# PCB_Fungnator.net
KiCad netlist of a schematic drawn in Altium Designer
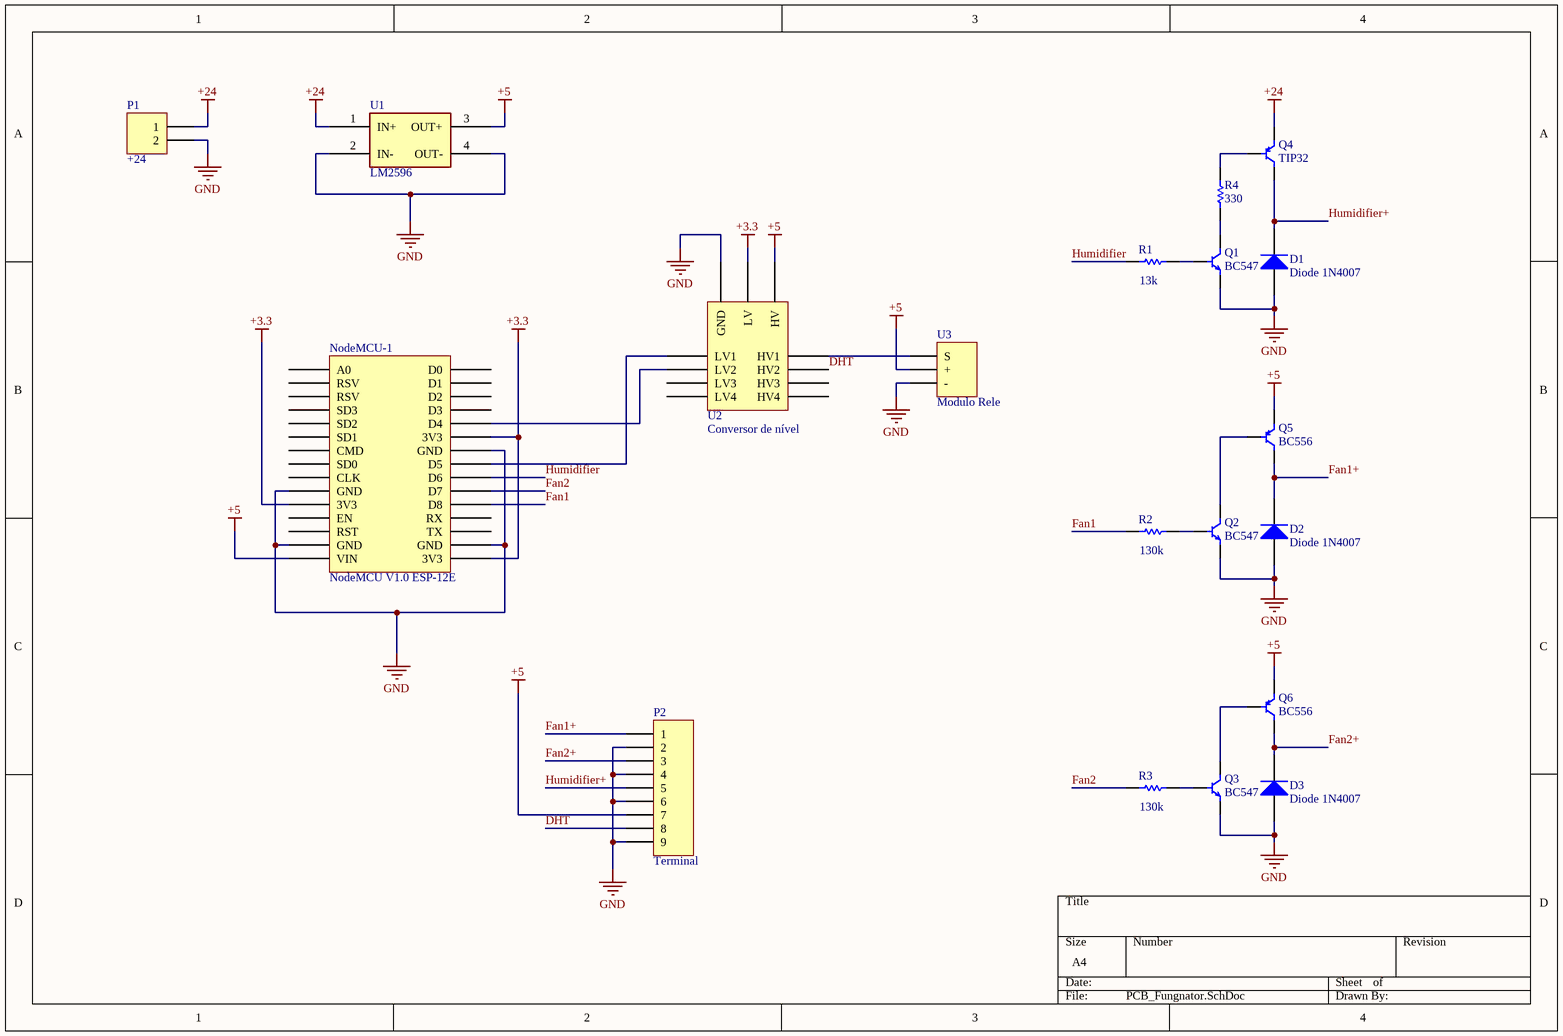
[diagram p0: PCB_Fungnator.SchDoc]

(export (version "E")
  (design (tool "Eeschema 10.0.6"))
  (components
    (comp (ref "D1")
      (value "Diode 1N4007")
      (footprint "DO-41")
      (description "1 Amp General Purpose Rectifier")
      (fields (field (name "PUBLISHER") "Altium Limited"))
      (libsource (lib "Miscellaneous Devices") (part "Diode 1N4007"))
    )
    (comp (ref "D2")
      (value "Diode 1N4007")
      (footprint "DO-41")
      (description "1 Amp General Purpose Rectifier")
      (fields (field (name "PUBLISHER") "Altium Limited"))
      (libsource (lib "Miscellaneous Devices") (part "Diode 1N4007"))
    )
    (comp (ref "D3")
      (value "Diode 1N4007")
      (footprint "DO-41")
      (description "1 Amp General Purpose Rectifier")
      (fields (field (name "PUBLISHER") "Altium Limited"))
      (libsource (lib "Miscellaneous Devices") (part "Diode 1N4007"))
    )
    (comp (ref "NodeMCU-1")
      (value "NodeMCU V1.0 ESP-12E")
      (footprint "NodeMCU V1.0 ESP-12E")
      (description "NodeMCU V1.0 ESP8266 (ESP-12E)")
      (libsource (lib "nodemcu") (part "NodeMCU V1.0 ESP-12E"))
    )
    (comp (ref "P1")
      (value "+24")
      (footprint "KRE_2")
      (description "Terminal Block 1x2")
      (libsource (lib "GPDSE") (part "KRE_2"))
    )
    (comp (ref "P2")
      (value "Terminal")
      (footprint "KRE_9")
      (description "Terminal Block 1x9")
      (libsource (lib "GPDSE") (part "KRE_9"))
    )
    (comp (ref "Q1")
      (value "BC547")
      (footprint "TO-92/CBE")
      (description "NPN Epitaxial Silicon Transistor")
      (fields (field (name "COMPLEMENTARY PART") "BC557"))
      (libsource (lib "GPDSE") (part "BC547"))
    )
    (comp (ref "Q2")
      (value "BC547")
      (footprint "TO-92/CBE")
      (description "NPN Epitaxial Silicon Transistor")
      (fields (field (name "COMPLEMENTARY PART") "BC557"))
      (libsource (lib "GPDSE") (part "BC547"))
    )
    (comp (ref "Q3")
      (value "BC547")
      (footprint "TO-92/CBE")
      (description "NPN Epitaxial Silicon Transistor")
      (fields (field (name "COMPLEMENTARY PART") "BC557"))
      (libsource (lib "GPDSE") (part "BC547"))
    )
    (comp (ref "Q4")
      (value "TIP32")
      (footprint "TO-220/BCE")
      (description "PNP Epitaxial Silicon Transistor")
      (fields (field (name "COMPLEMENTARY PART") "TIP31"))
      (libsource (lib "GPDSE") (part "TIP32"))
    )
    (comp (ref "Q5")
      (value "BC556")
      (footprint "TO-92/CBE")
      (description "PNP Epitaxial Silicon Transistor")
      (fields (field (name "COMPLEMENTARY PART") "BC546"))
      (libsource (lib "GPDSE") (part "BC556"))
    )
    (comp (ref "Q6")
      (value "BC556")
      (footprint "TO-92/CBE")
      (description "PNP Epitaxial Silicon Transistor")
      (fields (field (name "COMPLEMENTARY PART") "BC546"))
      (libsource (lib "GPDSE") (part "BC556"))
    )
    (comp (ref "R1")
      (value "13k")
      (footprint "AXIAL-0.3")
      (description "Resistor")
      (fields (field (name "Comment") "Res1") (field (name "PUBLISHER") "Altium Limited"))
      (libsource (lib "Miscellaneous Devices") (part "Res1"))
    )
    (comp (ref "R2")
      (value "130k")
      (footprint "AXIAL-0.3")
      (description "Resistor")
      (fields (field (name "Comment") "Res1") (field (name "PUBLISHER") "Altium Limited"))
      (libsource (lib "Miscellaneous Devices") (part "Res1"))
    )
    (comp (ref "R3")
      (value "130k")
      (footprint "AXIAL-0.3")
      (description "Resistor")
      (fields (field (name "Comment") "Res1") (field (name "PUBLISHER") "Altium Limited"))
      (libsource (lib "Miscellaneous Devices") (part "Res1"))
    )
    (comp (ref "R4")
      (value "330")
      (footprint "AXIAL-0.3")
      (description "Resistor")
      (fields (field (name "Comment") "Res1") (field (name "PUBLISHER") "Altium Limited"))
      (libsource (lib "Miscellaneous Devices") (part "Res1"))
    )
    (comp (ref "U1") (value "LM2596") (footprint "LM2596") (libsource (lib "Schlib1") (part "LM2596")))
    (comp (ref "U2")
      (value "Conversor de nível")
      (footprint "Conversor_Nivel")
      (libsource (lib "Schlib1") (part "Conversor de nível"))
    )
    (comp (ref "U3")
      (value "Modulo Rele")
      (footprint "MODULO_RELE")
      (libsource (lib "Schlib1") (part "Modulo Rele"))
    )
  )
  (nets
    (net (code "1") (name "+3.3") (class "Default")
      (node (ref "NodeMCU-1") (pin "3V3") (pinfunction "3V3_3V3") (pintype "passive"))
      (node (ref "U2") (pin "3") (pinfunction "LV_3") (pintype "passive"))
    )
    (net (code "2") (name "+5") (class "Default")
      (node (ref "NodeMCU-1") (pin "VIN") (pinfunction "VIN_VIN") (pintype "passive"))
      (node (ref "P2") (pin "7") (pinfunction "7_7") (pintype "passive"))
      (node (ref "Q5") (pin "E") (pinfunction "E_E") (pintype "passive"))
      (node (ref "Q6") (pin "E") (pinfunction "E_E") (pintype "passive"))
      (node (ref "U1") (pin "3") (pinfunction "OUT+_3") (pintype "passive"))
      (node (ref "U2") (pin "9") (pinfunction "HV_9") (pintype "passive"))
      (node (ref "U3") (pin "2") (pinfunction "+_2") (pintype "passive"))
    )
    (net (code "3") (name "+24") (class "Default")
      (node (ref "P1") (pin "1") (pinfunction "1_1") (pintype "passive"))
      (node (ref "Q4") (pin "E") (pinfunction "E_E") (pintype "passive"))
      (node (ref "U1") (pin "1") (pinfunction "IN+_1") (pintype "passive"))
    )
    (net (code "4") (name "/DHT") (class "Default")
      (node (ref "P2") (pin "8") (pinfunction "8_8") (pintype "passive"))
      (node (ref "U2") (pin "8") (pinfunction "HV2_8") (pintype "passive"))
    )
    (net (code "5") (name "/Fan1") (class "Default")
      (node (ref "NodeMCU-1") (pin "D8") (pinfunction "D8_D8") (pintype "passive"))
      (node (ref "R2") (pin "1") (pinfunction "1_1") (pintype "passive"))
    )
    (net (code "6") (name "/Fan1+") (class "Default")
      (node (ref "D2") (pin "2") (pinfunction "K_2") (pintype "passive"))
      (node (ref "P2") (pin "1") (pinfunction "1_1") (pintype "passive"))
      (node (ref "Q5") (pin "C") (pinfunction "C_C") (pintype "passive"))
    )
    (net (code "7") (name "/Fan2") (class "Default")
      (node (ref "NodeMCU-1") (pin "D7") (pinfunction "D7_D7") (pintype "passive"))
      (node (ref "R3") (pin "1") (pinfunction "1_1") (pintype "passive"))
    )
    (net (code "8") (name "/Fan2+") (class "Default")
      (node (ref "D3") (pin "2") (pinfunction "K_2") (pintype "passive"))
      (node (ref "P2") (pin "3") (pinfunction "3_3") (pintype "passive"))
      (node (ref "Q6") (pin "C") (pinfunction "C_C") (pintype "passive"))
    )
    (net (code "9") (name "/Humidifier") (class "Default")
      (node (ref "NodeMCU-1") (pin "D6") (pinfunction "D6_D6") (pintype "passive"))
      (node (ref "R1") (pin "1") (pinfunction "1_1") (pintype "passive"))
    )
    (net (code "10") (name "/Humidifier+") (class "Default")
      (node (ref "D1") (pin "2") (pinfunction "K_2") (pintype "passive"))
      (node (ref "P2") (pin "5") (pinfunction "5_5") (pintype "passive"))
      (node (ref "Q4") (pin "C") (pinfunction "C_C") (pintype "passive"))
    )
    (net (code "11") (name "GND") (class "Default")
      (node (ref "D1") (pin "1") (pinfunction "A_1") (pintype "passive"))
      (node (ref "D2") (pin "1") (pinfunction "A_1") (pintype "passive"))
      (node (ref "D3") (pin "1") (pinfunction "A_1") (pintype "passive"))
      (node (ref "NodeMCU-1") (pin "GND") (pinfunction "GND_GND") (pintype "passive"))
      (node (ref "P1") (pin "2") (pinfunction "2_2") (pintype "passive"))
      (node (ref "P2") (pin "2") (pinfunction "2_2") (pintype "passive"))
      (node (ref "P2") (pin "4") (pinfunction "4_4") (pintype "passive"))
      (node (ref "P2") (pin "6") (pinfunction "6_6") (pintype "passive"))
      (node (ref "P2") (pin "9") (pinfunction "9_9") (pintype "passive"))
      (node (ref "Q1") (pin "E") (pinfunction "E_E") (pintype "passive"))
      (node (ref "Q2") (pin "E") (pinfunction "E_E") (pintype "passive"))
      (node (ref "Q3") (pin "E") (pinfunction "E_E") (pintype "passive"))
      (node (ref "U1") (pin "2") (pinfunction "IN-_2") (pintype "passive"))
      (node (ref "U1") (pin "4") (pinfunction "OUT-_4") (pintype "passive"))
      (node (ref "U2") (pin "4") (pinfunction "GND_4") (pintype "passive"))
      (node (ref "U3") (pin "3") (pinfunction "-_3") (pintype "passive"))
    )
    (net (code "12") (name "Net-(Q1-PadB)") (class "Default")
      (node (ref "Q1") (pin "B") (pinfunction "B_B") (pintype "passive"))
      (node (ref "R1") (pin "2") (pinfunction "2_2") (pintype "passive"))
    )
    (net (code "13") (name "Net-(Q1-PadC)") (class "Default")
      (node (ref "Q1") (pin "C") (pinfunction "C_C") (pintype "passive"))
      (node (ref "R4") (pin "1") (pinfunction "1_1") (pintype "passive"))
    )
    (net (code "14") (name "Net-(Q2-PadB)") (class "Default")
      (node (ref "Q2") (pin "B") (pinfunction "B_B") (pintype "passive"))
      (node (ref "R2") (pin "2") (pinfunction "2_2") (pintype "passive"))
    )
    (net (code "15") (name "Net-(Q2-PadC)") (class "Default")
      (node (ref "Q2") (pin "C") (pinfunction "C_C") (pintype "passive"))
      (node (ref "Q5") (pin "B") (pinfunction "B_B") (pintype "passive"))
    )
    (net (code "16") (name "Net-(Q3-PadB)") (class "Default")
      (node (ref "Q3") (pin "B") (pinfunction "B_B") (pintype "passive"))
      (node (ref "R3") (pin "2") (pinfunction "2_2") (pintype "passive"))
    )
    (net (code "17") (name "Net-(Q3-PadC)") (class "Default")
      (node (ref "Q3") (pin "C") (pinfunction "C_C") (pintype "passive"))
      (node (ref "Q6") (pin "B") (pinfunction "B_B") (pintype "passive"))
    )
    (net (code "18") (name "Net-(Q4-PadB)") (class "Default")
      (node (ref "Q4") (pin "B") (pinfunction "B_B") (pintype "passive"))
      (node (ref "R4") (pin "2") (pinfunction "2_2") (pintype "passive"))
    )
    (net (code "19") (name "Net-(U2-HV1)") (class "Default")
      (node (ref "U2") (pin "7") (pinfunction "HV1_7") (pintype "passive"))
      (node (ref "U3") (pin "1") (pinfunction "S_1") (pintype "passive"))
    )
    (net (code "20") (name "Net-(U2-LV1)") (class "Default")
      (node (ref "NodeMCU-1") (pin "D5") (pinfunction "D5_D5") (pintype "passive"))
      (node (ref "U2") (pin "1") (pinfunction "LV1_1") (pintype "passive"))
    )
    (net (code "21") (name "Net-(U2-LV2)") (class "Default")
      (node (ref "NodeMCU-1") (pin "D4") (pinfunction "D4_D4") (pintype "passive"))
      (node (ref "U2") (pin "2") (pinfunction "LV2_2") (pintype "passive"))
    )
    (net (code "22") (name "unconnected-(NodeMCU-1-PadA0)") (class "Default")
      (node (ref "NodeMCU-1") (pin "A0") (pinfunction "A0_A0") (pintype "passive"))
    )
    (net (code "23") (name "unconnected-(NodeMCU-1-PadCLK)") (class "Default")
      (node (ref "NodeMCU-1") (pin "CLK") (pinfunction "CLK_CLK") (pintype "passive"))
    )
    (net (code "24") (name "unconnected-(NodeMCU-1-PadCMD)") (class "Default")
      (node (ref "NodeMCU-1") (pin "CMD") (pinfunction "CMD_CMD") (pintype "passive"))
    )
    (net (code "25") (name "unconnected-(NodeMCU-1-PadD0)") (class "Default")
      (node (ref "NodeMCU-1") (pin "D0") (pinfunction "D0_D0") (pintype "passive"))
    )
    (net (code "26") (name "unconnected-(NodeMCU-1-PadD1)") (class "Default")
      (node (ref "NodeMCU-1") (pin "D1") (pinfunction "D1_D1") (pintype "passive"))
    )
    (net (code "27") (name "unconnected-(NodeMCU-1-PadD2)") (class "Default")
      (node (ref "NodeMCU-1") (pin "D2") (pinfunction "D2_D2") (pintype "passive"))
    )
    (net (code "28") (name "unconnected-(NodeMCU-1-PadD3)") (class "Default")
      (node (ref "NodeMCU-1") (pin "D3") (pinfunction "D3_D3") (pintype "passive"))
    )
    (net (code "29") (name "unconnected-(NodeMCU-1-PadEN)") (class "Default")
      (node (ref "NodeMCU-1") (pin "EN") (pinfunction "EN_EN") (pintype "passive"))
    )
    (net (code "30") (name "unconnected-(NodeMCU-1-PadRST)") (class "Default")
      (node (ref "NodeMCU-1") (pin "RST") (pinfunction "RST_RST") (pintype "passive"))
    )
    (net (code "31") (name "unconnected-(NodeMCU-1-PadRSV)") (class "Default")
      (node (ref "NodeMCU-1") (pin "RSV") (pinfunction "RSV_RSV") (pintype "passive"))
    )
    (net (code "32") (name "unconnected-(NodeMCU-1-PadRSV)_1") (class "Default")
      (node (ref "NodeMCU-1") (pin "RSV") (pinfunction "RSV_RSV") (pintype "passive"))
    )
    (net (code "33") (name "unconnected-(NodeMCU-1-PadRX)") (class "Default")
      (node (ref "NodeMCU-1") (pin "RX") (pinfunction "RX_RX") (pintype "passive"))
    )
    (net (code "34") (name "unconnected-(NodeMCU-1-PadSD0)") (class "Default")
      (node (ref "NodeMCU-1") (pin "SD0") (pinfunction "SD0_SD0") (pintype "passive"))
    )
    (net (code "35") (name "unconnected-(NodeMCU-1-PadSD1)") (class "Default")
      (node (ref "NodeMCU-1") (pin "SD1") (pinfunction "SD1_SD1") (pintype "passive"))
    )
    (net (code "36") (name "unconnected-(NodeMCU-1-PadSD2)") (class "Default")
      (node (ref "NodeMCU-1") (pin "SD2") (pinfunction "SD2_SD2") (pintype "passive"))
    )
    (net (code "37") (name "unconnected-(NodeMCU-1-PadSD3)") (class "Default")
      (node (ref "NodeMCU-1") (pin "SD3") (pinfunction "SD3_SD3") (pintype "passive"))
    )
    (net (code "38") (name "unconnected-(NodeMCU-1-PadTX)") (class "Default")
      (node (ref "NodeMCU-1") (pin "TX") (pinfunction "TX_TX") (pintype "passive"))
    )
    (net (code "39") (name "unconnected-(U2-HV3-Pad11)") (class "Default")
      (node (ref "U2") (pin "11") (pinfunction "HV3_11") (pintype "passive"))
    )
    (net (code "40") (name "unconnected-(U2-HV4-Pad12)") (class "Default")
      (node (ref "U2") (pin "12") (pinfunction "HV4_12") (pintype "passive"))
    )
    (net (code "41") (name "unconnected-(U2-LV3-Pad5)") (class "Default")
      (node (ref "U2") (pin "5") (pinfunction "LV3_5") (pintype "passive"))
    )
    (net (code "42") (name "unconnected-(U2-LV4-Pad6)") (class "Default")
      (node (ref "U2") (pin "6") (pinfunction "LV4_6") (pintype "passive"))
    )
  )
)
